# expansion-sn76489-kempton-sd-rev4b.net
KiCad netlist of a schematic drawn in EAGLE
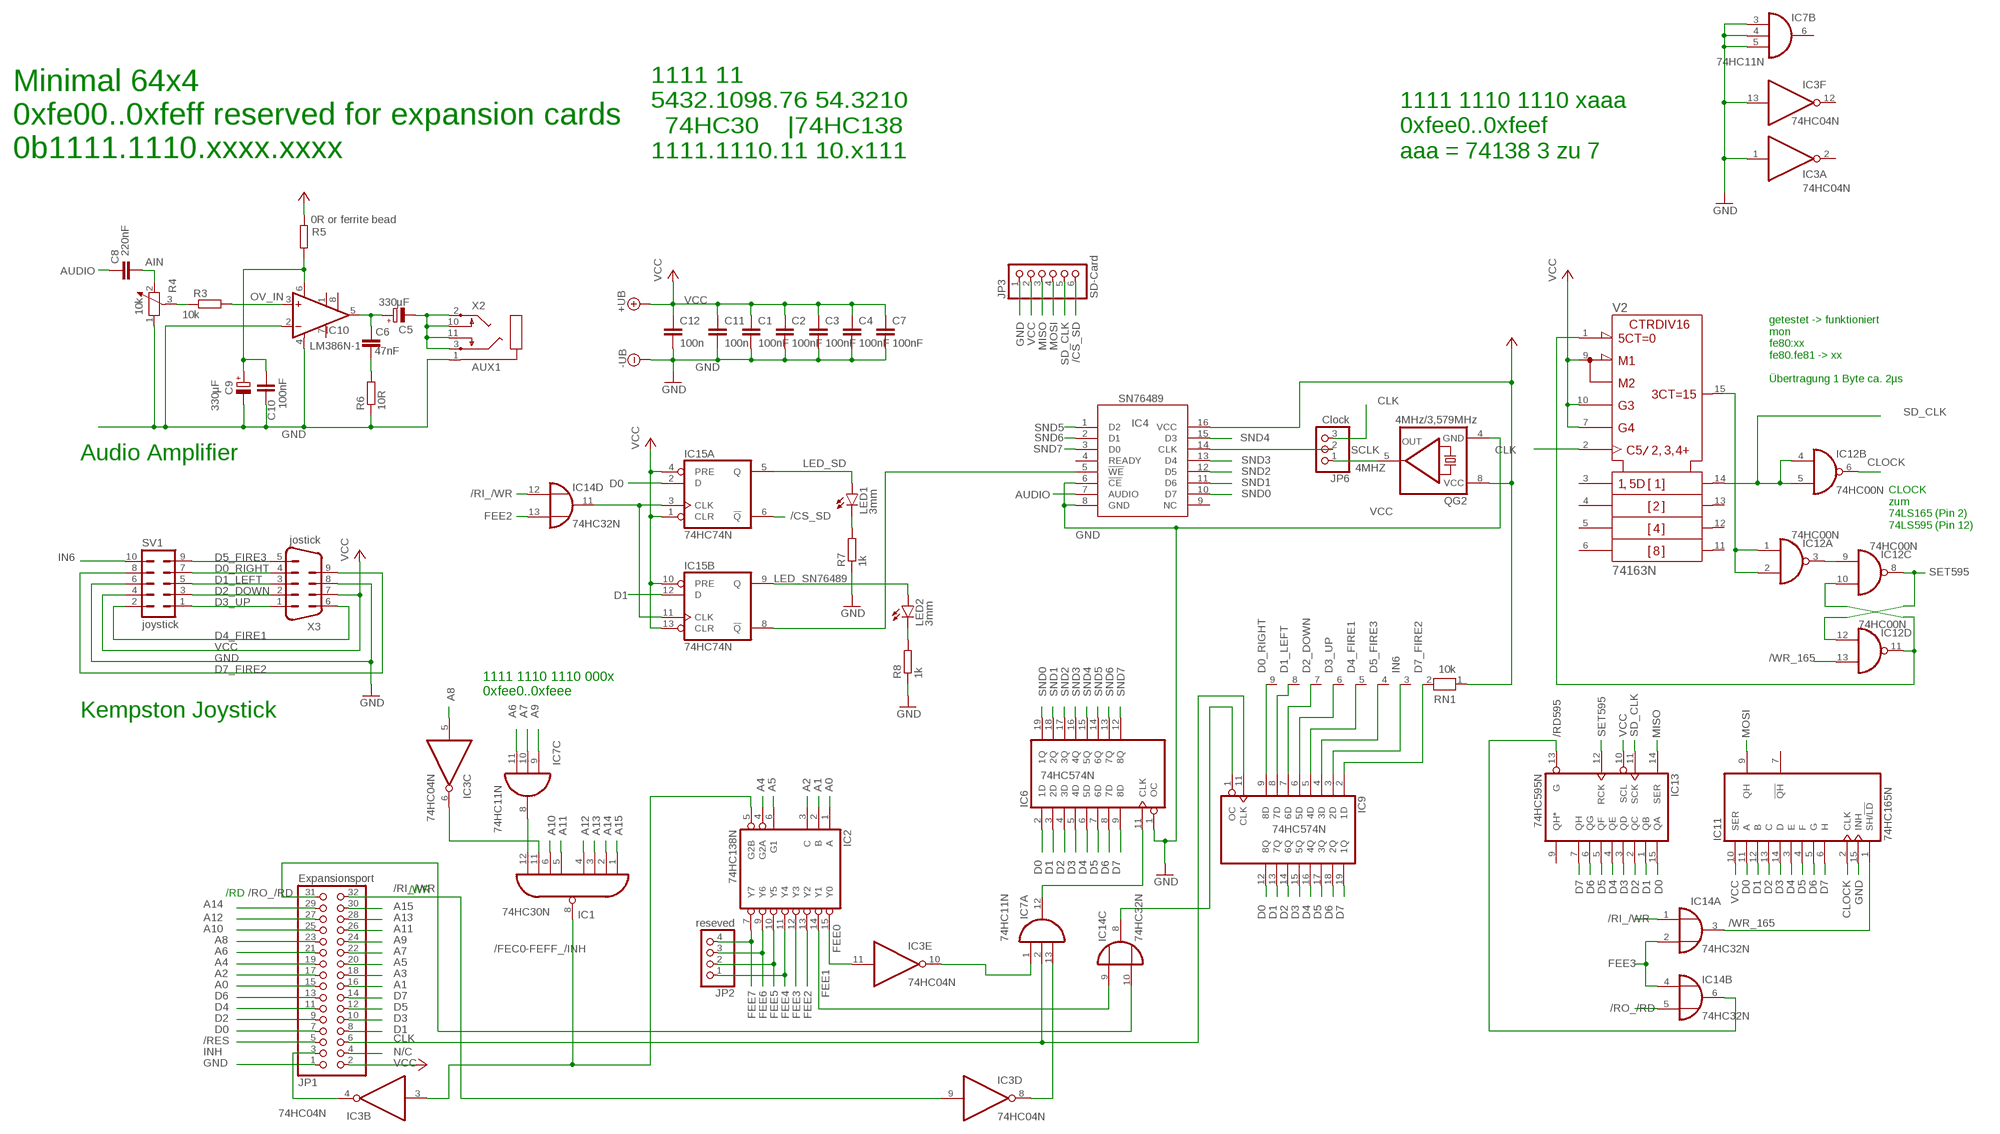
[diagram p0: schematic, sheet 1]

(export (version "E")
  (design (tool "Eeschema 10.0.6"))
  (components
    (comp (ref "C1")
      (value "100nF")
      (footprint "eagle-import:C050-025X075")
      (libsource (lib "eagle-import") (part "C-EU050-025X075"))
    )
    (comp (ref "C2")
      (value "100nF")
      (footprint "eagle-import:C050-025X075")
      (libsource (lib "eagle-import") (part "C-EU050-025X075"))
    )
    (comp (ref "C3")
      (value "100nF")
      (footprint "eagle-import:C050-025X075")
      (libsource (lib "eagle-import") (part "C-EU050-025X075"))
    )
    (comp (ref "C4")
      (value "100nF")
      (footprint "eagle-import:C050-025X075")
      (libsource (lib "eagle-import") (part "C-EU050-025X075"))
    )
    (comp (ref "C5")
      (value "330µF")
      (footprint "eagle-import:E2,5-7")
      (libsource (lib "eagle-import") (part "CPOL-EUE2.5-7"))
    )
    (comp (ref "C6")
      (value "47nF")
      (footprint "eagle-import:C050-025X075")
      (libsource (lib "eagle-import") (part "C-EU050-025X075"))
    )
    (comp (ref "C7")
      (value "100nF")
      (footprint "eagle-import:C050-025X075")
      (libsource (lib "eagle-import") (part "C-EU050-025X075"))
    )
    (comp (ref "C8")
      (value "220nF")
      (footprint "eagle-import:C050-025X075")
      (libsource (lib "eagle-import") (part "C-EU050-025X075"))
    )
    (comp (ref "C9")
      (value "330µF")
      (footprint "eagle-import:E2,5-7")
      (libsource (lib "eagle-import") (part "CPOL-EUE2.5-7"))
    )
    (comp (ref "C10")
      (value "100nF")
      (footprint "eagle-import:C050-025X075")
      (libsource (lib "eagle-import") (part "C-EU050-025X075"))
    )
    (comp (ref "C11")
      (value "100n")
      (footprint "eagle-import:C050-025X075")
      (libsource (lib "eagle-import") (part "C-EU050-025X075"))
    )
    (comp (ref "C12")
      (value "100n")
      (footprint "eagle-import:C050-025X075")
      (libsource (lib "eagle-import") (part "C-EU050-025X075"))
    )
    (comp (ref "IC1")
      (value "74HC30N")
      (footprint "eagle-import:DIL14")
      (libsource (lib "eagle-import") (part "7430NHC"))
    )
    (comp (ref "IC2")
      (value "74HC138N")
      (footprint "eagle-import:DIL16")
      (libsource (lib "eagle-import") (part "74138NHC"))
    )
    (comp (ref "IC3")
      (value "74HC04N")
      (footprint "eagle-import:DIL14")
      (libsource (lib "eagle-import") (part "7404NHC"))
    )
    (comp (ref "IC4")
      (value "SN76489")
      (footprint "eagle-import:ALEX-PARTS_DIL16")
      (libsource (lib "eagle-import") (part "ALEX-PARTS_SN76489AN"))
    )
    (comp (ref "IC6")
      (value "74HC574N")
      (footprint "eagle-import:DIL20")
      (libsource (lib "eagle-import") (part "74574NHC"))
    )
    (comp (ref "IC7")
      (value "74HC11N")
      (footprint "eagle-import:DIL14")
      (libsource (lib "eagle-import") (part "7411NHC"))
    )
    (comp (ref "IC9")
      (value "74HC574N")
      (footprint "eagle-import:DIL20")
      (libsource (lib "eagle-import") (part "74574NHC"))
    )
    (comp (ref "IC10")
      (value "LM386N-1")
      (footprint "eagle-import:DIL08")
      (libsource (lib "eagle-import") (part "LM386?-N1"))
    )
    (comp (ref "IC11")
      (value "74HC165N")
      (footprint "eagle-import:DIL16")
      (libsource (lib "eagle-import") (part "74165NHC"))
    )
    (comp (ref "IC12")
      (value "74HC00N")
      (footprint "eagle-import:DIL14")
      (libsource (lib "eagle-import") (part "7400NHC"))
    )
    (comp (ref "IC13")
      (value "74HC595N")
      (footprint "eagle-import:DIL16")
      (libsource (lib "eagle-import") (part "74595NHC"))
    )
    (comp (ref "IC14")
      (value "74HC32N")
      (footprint "eagle-import:DIL14")
      (libsource (lib "eagle-import") (part "7432NHC"))
    )
    (comp (ref "IC15")
      (value "74HC74N")
      (footprint "eagle-import:DIL14")
      (libsource (lib "eagle-import") (part "7474NHC"))
    )
    (comp (ref "JP1")
      (value "Expansionsport")
      (footprint "eagle-import:2X16")
      (libsource (lib "eagle-import") (part "PINHD-2X16"))
    )
    (comp (ref "JP2")
      (value "reseved")
      (footprint "eagle-import:1X04")
      (libsource (lib "eagle-import") (part "PINHD-1X4"))
    )
    (comp (ref "JP3")
      (value "SD-Card")
      (footprint "eagle-import:1X06")
      (libsource (lib "eagle-import") (part "PINHD-1X6"))
    )
    (comp (ref "JP6")
      (value "Clock")
      (footprint "eagle-import:1X03")
      (libsource (lib "eagle-import") (part "PINHD-1X3"))
    )
    (comp (ref "LED1")
      (value "3mm")
      (footprint "eagle-import:LED3MM")
      (libsource (lib "eagle-import") (part "LED3MM"))
    )
    (comp (ref "LED2")
      (value "3mm")
      (footprint "eagle-import:LED3MM")
      (libsource (lib "eagle-import") (part "LED3MM"))
    )
    (comp (ref "QG2")
      (value "4MHz/3,579MHz")
      (footprint "eagle-import:DIL08S")
      (libsource (lib "eagle-import") (part "QG5460"))
    )
    (comp (ref "R3")
      (value "10k")
      (footprint "eagle-import:0207_10")
      (libsource (lib "eagle-import") (part "R-EU_0207/10"))
    )
    (comp (ref "R4")
      (value "10k")
      (footprint "eagle-import:PT-10S")
      (libsource (lib "eagle-import") (part "POTENTIOMETER_PT-10S"))
    )
    (comp (ref "R5")
      (value "0R or ferrite bead")
      (footprint "eagle-import:0207_10")
      (libsource (lib "eagle-import") (part "R-EU_0207/10"))
    )
    (comp (ref "R6")
      (value "10R")
      (footprint "eagle-import:0207_10")
      (libsource (lib "eagle-import") (part "R-EU_0207/10"))
    )
    (comp (ref "R7")
      (value "1k")
      (footprint "eagle-import:0207_10")
      (libsource (lib "eagle-import") (part "R-EU_0207/10"))
    )
    (comp (ref "R8")
      (value "1k")
      (footprint "eagle-import:0207_10")
      (libsource (lib "eagle-import") (part "R-EU_0207/10"))
    )
    (comp (ref "RN1")
      (value "10k")
      (footprint "eagle-import:RN-9")
      (libsource (lib "eagle-import") (part "RN08"))
    )
    (comp (ref "SV1")
      (value "joystick")
      (footprint "eagle-import:ML10")
      (libsource (lib "eagle-import") (part "ML10"))
    )
    (comp (ref "V2")
      (value "74163N")
      (footprint "eagle-import:DIL16")
      (libsource (lib "eagle-import") (part "74163N"))
    )
    (comp (ref "X2")
      (value "AUX1")
      (footprint "eagle-import:SJ1-352XN")
      (libsource (lib "eagle-import") (part "CON-SJ1-352XNSJ1-352XN"))
    )
    (comp (ref "X3")
      (value "jostick")
      (footprint "eagle-import:182-009-MALE")
      (libsource (lib "eagle-import") (part "M09-182"))
    )
  )
  (nets
    (net (code "1") (name "+UB") (class "Default")
      (node (ref "C1") (pin "1") (pinfunction "1_1") (pintype "passive"))
      (node (ref "C11") (pin "1") (pinfunction "1_1") (pintype "passive"))
      (node (ref "C12") (pin "1") (pinfunction "1_1") (pintype "passive"))
      (node (ref "C2") (pin "1") (pinfunction "1_1") (pintype "passive"))
      (node (ref "C3") (pin "1") (pinfunction "1_1") (pintype "passive"))
      (node (ref "C4") (pin "1") (pinfunction "1_1") (pintype "passive"))
      (node (ref "C7") (pin "1") (pinfunction "1_1") (pintype "passive"))
      (node (ref "IC11") (pin "10") (pinfunction "SER_10") (pintype "input"))
      (node (ref "IC13") (pin "10") (pinfunction "SCL_10") (pintype "input"))
      (node (ref "IC15") (pin "1") (pinfunction "CLR_1") (pintype "input"))
      (node (ref "IC15") (pin "10") (pinfunction "PRE_10") (pintype "input"))
      (node (ref "IC15") (pin "13") (pinfunction "CLR_13") (pintype "input"))
      (node (ref "IC15") (pin "4") (pinfunction "PRE_4") (pintype "input"))
      (node (ref "IC4") (pin "16") (pinfunction "VCC_16") (pintype "input"))
      (node (ref "JP1") (pin "2") (pinfunction "2_2") (pintype "passive"))
      (node (ref "JP3") (pin "2") (pinfunction "2_2") (pintype "passive"))
      (node (ref "QG2") (pin "8") (pinfunction "VCC_8") (pintype "power_in"))
      (node (ref "R5") (pin "2") (pinfunction "2_2") (pintype "passive"))
      (node (ref "RN1") (pin "1") (pinfunction "1_1") (pintype "passive"))
      (node (ref "SV1") (pin "4") (pinfunction "4_4") (pintype "passive"))
      (node (ref "V2") (pin "10") (pinfunction "ENT_10") (pintype "input"))
      (node (ref "V2") (pin "7") (pinfunction "ENP_7") (pintype "input"))
      (node (ref "V2") (pin "9") (pinfunction "~{LOAD}_9") (pintype "input"))
      (node (ref "X3") (pin "7") (pinfunction "7_7") (pintype "passive"))
    )
    (net (code "2") (name "-UB") (class "Default")
      (node (ref "C1") (pin "2") (pinfunction "2_2") (pintype "passive"))
      (node (ref "C10") (pin "2") (pinfunction "2_2") (pintype "passive"))
      (node (ref "C11") (pin "2") (pinfunction "2_2") (pintype "passive"))
      (node (ref "C12") (pin "2") (pinfunction "2_2") (pintype "passive"))
      (node (ref "C2") (pin "2") (pinfunction "2_2") (pintype "passive"))
      (node (ref "C3") (pin "2") (pinfunction "2_2") (pintype "passive"))
      (node (ref "C4") (pin "2") (pinfunction "2_2") (pintype "passive"))
      (node (ref "C7") (pin "2") (pinfunction "2_2") (pintype "passive"))
      (node (ref "C9") (pin "-") (pinfunction "-_-") (pintype "passive"))
      (node (ref "IC10") (pin "2") (pinfunction "-IN_2") (pintype "input"))
      (node (ref "IC10") (pin "4") (pinfunction "GND_4") (pintype "power_in"))
      (node (ref "IC11") (pin "15") (pinfunction "INH_15") (pintype "input"))
      (node (ref "IC3") (pin "1") (pinfunction "I_1") (pintype "input"))
      (node (ref "IC3") (pin "13") (pinfunction "I_13") (pintype "input"))
      (node (ref "IC4") (pin "6") (pinfunction "~{CE}_6") (pintype "input"))
      (node (ref "IC4") (pin "8") (pinfunction "GND_8") (pintype "power_in"))
      (node (ref "IC6") (pin "1") (pinfunction "OC_1") (pintype "input"))
      (node (ref "IC7") (pin "3") (pinfunction "I0_3") (pintype "input"))
      (node (ref "IC7") (pin "4") (pinfunction "I1_4") (pintype "input"))
      (node (ref "IC7") (pin "5") (pinfunction "I2_5") (pintype "input"))
      (node (ref "JP1") (pin "1") (pinfunction "1_1") (pintype "passive"))
      (node (ref "JP3") (pin "1") (pinfunction "1_1") (pintype "passive"))
      (node (ref "QG2") (pin "4") (pinfunction "GND_4") (pintype "power_in"))
      (node (ref "R4") (pin "1") (pinfunction "1_1") (pintype "passive"))
      (node (ref "R6") (pin "1") (pinfunction "1_1") (pintype "passive"))
      (node (ref "R7") (pin "1") (pinfunction "1_1") (pintype "passive"))
      (node (ref "R8") (pin "1") (pinfunction "1_1") (pintype "passive"))
      (node (ref "SV1") (pin "6") (pinfunction "6_6") (pintype "passive"))
      (node (ref "X2") (pin "1") (pinfunction "1_1") (pintype "passive"))
      (node (ref "X3") (pin "8") (pinfunction "8_8") (pintype "passive"))
    )
    (net (code "3") (name "/4MHZ") (class "Default")
      (node (ref "JP6") (pin "1") (pinfunction "1_1") (pintype "passive"))
      (node (ref "QG2") (pin "5") (pinfunction "OUT_5") (pintype "output"))
    )
    (net (code "4") (name "/A0") (class "Default")
      (node (ref "IC2") (pin "1") (pinfunction "A_1") (pintype "input"))
      (node (ref "JP1") (pin "15") (pinfunction "15_15") (pintype "passive"))
    )
    (net (code "5") (name "/A1") (class "Default")
      (node (ref "IC2") (pin "2") (pinfunction "B_2") (pintype "input"))
      (node (ref "JP1") (pin "16") (pinfunction "16_16") (pintype "passive"))
    )
    (net (code "6") (name "/A2") (class "Default")
      (node (ref "IC2") (pin "3") (pinfunction "C_3") (pintype "input"))
      (node (ref "JP1") (pin "17") (pinfunction "17_17") (pintype "passive"))
    )
    (net (code "7") (name "/A3") (class "Default")
      (node (ref "JP1") (pin "18") (pinfunction "18_18") (pintype "passive"))
    )
    (net (code "8") (name "/A4") (class "Default")
      (node (ref "IC2") (pin "4") (pinfunction "G2A_4") (pintype "input"))
      (node (ref "JP1") (pin "19") (pinfunction "19_19") (pintype "passive"))
    )
    (net (code "9") (name "/A5") (class "Default")
      (node (ref "IC2") (pin "6") (pinfunction "G1_6") (pintype "input"))
      (node (ref "JP1") (pin "20") (pinfunction "20_20") (pintype "passive"))
    )
    (net (code "10") (name "/A6") (class "Default")
      (node (ref "IC7") (pin "11") (pinfunction "I2_11") (pintype "input"))
      (node (ref "JP1") (pin "21") (pinfunction "21_21") (pintype "passive"))
    )
    (net (code "11") (name "/A7") (class "Default")
      (node (ref "IC7") (pin "10") (pinfunction "I1_10") (pintype "input"))
      (node (ref "JP1") (pin "22") (pinfunction "22_22") (pintype "passive"))
    )
    (net (code "12") (name "/A8") (class "Default")
      (node (ref "IC3") (pin "5") (pinfunction "I_5") (pintype "input"))
      (node (ref "JP1") (pin "23") (pinfunction "23_23") (pintype "passive"))
    )
    (net (code "13") (name "/A9") (class "Default")
      (node (ref "IC7") (pin "9") (pinfunction "I0_9") (pintype "input"))
      (node (ref "JP1") (pin "24") (pinfunction "24_24") (pintype "passive"))
    )
    (net (code "14") (name "/A10") (class "Default")
      (node (ref "IC1") (pin "6") (pinfunction "I5_6") (pintype "input"))
      (node (ref "JP1") (pin "25") (pinfunction "25_25") (pintype "passive"))
    )
    (net (code "15") (name "/A11") (class "Default")
      (node (ref "IC1") (pin "5") (pinfunction "I4_5") (pintype "input"))
      (node (ref "JP1") (pin "26") (pinfunction "26_26") (pintype "passive"))
    )
    (net (code "16") (name "/A12") (class "Default")
      (node (ref "IC1") (pin "4") (pinfunction "I3_4") (pintype "input"))
      (node (ref "JP1") (pin "27") (pinfunction "27_27") (pintype "passive"))
    )
    (net (code "17") (name "/A13") (class "Default")
      (node (ref "IC1") (pin "3") (pinfunction "I2_3") (pintype "input"))
      (node (ref "JP1") (pin "28") (pinfunction "28_28") (pintype "passive"))
    )
    (net (code "18") (name "/A14") (class "Default")
      (node (ref "IC1") (pin "2") (pinfunction "I1_2") (pintype "input"))
      (node (ref "JP1") (pin "29") (pinfunction "29_29") (pintype "passive"))
    )
    (net (code "19") (name "/A15") (class "Default")
      (node (ref "IC1") (pin "1") (pinfunction "I0_1") (pintype "input"))
      (node (ref "JP1") (pin "30") (pinfunction "30_30") (pintype "passive"))
    )
    (net (code "20") (name "/AIN") (class "Default")
      (node (ref "C8") (pin "2") (pinfunction "2_2") (pintype "passive"))
      (node (ref "R4") (pin "2") (pinfunction "2_2") (pintype "passive"))
    )
    (net (code "21") (name "/AUDIO") (class "Default")
      (node (ref "C8") (pin "1") (pinfunction "1_1") (pintype "passive"))
      (node (ref "IC4") (pin "7") (pinfunction "AUDIO_7") (pintype "output"))
    )
    (net (code "22") (name "/CLK") (class "Default")
      (node (ref "IC7") (pin "2") (pinfunction "I1_2") (pintype "input"))
      (node (ref "IC9") (pin "11") (pinfunction "CLK_11") (pintype "input"))
      (node (ref "JP1") (pin "6") (pinfunction "6_6") (pintype "passive"))
      (node (ref "JP6") (pin "3") (pinfunction "3_3") (pintype "passive"))
      (node (ref "V2") (pin "2") (pinfunction "CLK_2") (pintype "input"))
    )
    (net (code "23") (name "/CLOCK") (class "Default")
      (node (ref "IC11") (pin "2") (pinfunction "CLK_2") (pintype "input"))
      (node (ref "IC12") (pin "6") (pinfunction "O_6") (pintype "output"))
    )
    (net (code "24") (name "/D0") (class "Default")
      (node (ref "IC11") (pin "11") (pinfunction "A_11") (pintype "input"))
      (node (ref "IC13") (pin "15") (pinfunction "QA_15") (pintype "tri_state"))
      (node (ref "IC15") (pin "2") (pinfunction "D_2") (pintype "input"))
      (node (ref "IC6") (pin "2") (pinfunction "1D_2") (pintype "input"))
      (node (ref "IC9") (pin "12") (pinfunction "8Q_12") (pintype "tri_state"))
      (node (ref "JP1") (pin "7") (pinfunction "7_7") (pintype "passive"))
    )
    (net (code "25") (name "/D0_RIGHT") (class "Default")
      (node (ref "IC9") (pin "9") (pinfunction "8D_9") (pintype "input"))
      (node (ref "RN1") (pin "9") (pinfunction "9_9") (pintype "passive"))
      (node (ref "SV1") (pin "7") (pinfunction "7_7") (pintype "passive"))
      (node (ref "X3") (pin "4") (pinfunction "4_4") (pintype "passive"))
    )
    (net (code "26") (name "/D1") (class "Default")
      (node (ref "IC11") (pin "12") (pinfunction "B_12") (pintype "input"))
      (node (ref "IC13") (pin "1") (pinfunction "QB_1") (pintype "tri_state"))
      (node (ref "IC15") (pin "12") (pinfunction "D_12") (pintype "input"))
      (node (ref "IC6") (pin "3") (pinfunction "2D_3") (pintype "input"))
      (node (ref "IC9") (pin "13") (pinfunction "7Q_13") (pintype "tri_state"))
      (node (ref "JP1") (pin "8") (pinfunction "8_8") (pintype "passive"))
    )
    (net (code "27") (name "/D1_LEFT") (class "Default")
      (node (ref "IC9") (pin "8") (pinfunction "7D_8") (pintype "input"))
      (node (ref "RN1") (pin "8") (pinfunction "8_8") (pintype "passive"))
      (node (ref "SV1") (pin "5") (pinfunction "5_5") (pintype "passive"))
      (node (ref "X3") (pin "3") (pinfunction "3_3") (pintype "passive"))
    )
    (net (code "28") (name "/D2") (class "Default")
      (node (ref "IC11") (pin "13") (pinfunction "C_13") (pintype "input"))
      (node (ref "IC13") (pin "2") (pinfunction "QC_2") (pintype "tri_state"))
      (node (ref "IC6") (pin "4") (pinfunction "3D_4") (pintype "input"))
      (node (ref "IC9") (pin "14") (pinfunction "6Q_14") (pintype "tri_state"))
      (node (ref "JP1") (pin "9") (pinfunction "9_9") (pintype "passive"))
    )
    (net (code "29") (name "/D2_DOWN") (class "Default")
      (node (ref "IC9") (pin "7") (pinfunction "6D_7") (pintype "input"))
      (node (ref "RN1") (pin "7") (pinfunction "7_7") (pintype "passive"))
      (node (ref "SV1") (pin "3") (pinfunction "3_3") (pintype "passive"))
      (node (ref "X3") (pin "2") (pinfunction "2_2") (pintype "passive"))
    )
    (net (code "30") (name "/D3") (class "Default")
      (node (ref "IC11") (pin "14") (pinfunction "D_14") (pintype "input"))
      (node (ref "IC13") (pin "3") (pinfunction "QD_3") (pintype "tri_state"))
      (node (ref "IC6") (pin "5") (pinfunction "4D_5") (pintype "input"))
      (node (ref "IC9") (pin "15") (pinfunction "5Q_15") (pintype "tri_state"))
      (node (ref "JP1") (pin "10") (pinfunction "10_10") (pintype "passive"))
    )
    (net (code "31") (name "/D3_UP") (class "Default")
      (node (ref "IC9") (pin "6") (pinfunction "5D_6") (pintype "input"))
      (node (ref "RN1") (pin "6") (pinfunction "6_6") (pintype "passive"))
      (node (ref "SV1") (pin "1") (pinfunction "1_1") (pintype "passive"))
      (node (ref "X3") (pin "1") (pinfunction "1_1") (pintype "passive"))
    )
    (net (code "32") (name "/D4") (class "Default")
      (node (ref "IC11") (pin "3") (pinfunction "E_3") (pintype "input"))
      (node (ref "IC13") (pin "4") (pinfunction "QE_4") (pintype "tri_state"))
      (node (ref "IC6") (pin "6") (pinfunction "5D_6") (pintype "input"))
      (node (ref "IC9") (pin "16") (pinfunction "4Q_16") (pintype "tri_state"))
      (node (ref "JP1") (pin "11") (pinfunction "11_11") (pintype "passive"))
    )
    (net (code "33") (name "/D4_FIRE1") (class "Default")
      (node (ref "IC9") (pin "5") (pinfunction "4D_5") (pintype "input"))
      (node (ref "RN1") (pin "5") (pinfunction "5_5") (pintype "passive"))
      (node (ref "SV1") (pin "2") (pinfunction "2_2") (pintype "passive"))
      (node (ref "X3") (pin "6") (pinfunction "6_6") (pintype "passive"))
    )
    (net (code "34") (name "/D5") (class "Default")
      (node (ref "IC11") (pin "4") (pinfunction "F_4") (pintype "input"))
      (node (ref "IC13") (pin "5") (pinfunction "QF_5") (pintype "tri_state"))
      (node (ref "IC6") (pin "7") (pinfunction "6D_7") (pintype "input"))
      (node (ref "IC9") (pin "17") (pinfunction "3Q_17") (pintype "tri_state"))
      (node (ref "JP1") (pin "12") (pinfunction "12_12") (pintype "passive"))
    )
    (net (code "35") (name "/D5_FIRE3") (class "Default")
      (node (ref "IC9") (pin "4") (pinfunction "3D_4") (pintype "input"))
      (node (ref "RN1") (pin "4") (pinfunction "4_4") (pintype "passive"))
      (node (ref "SV1") (pin "9") (pinfunction "9_9") (pintype "passive"))
      (node (ref "X3") (pin "5") (pinfunction "5_5") (pintype "passive"))
    )
    (net (code "36") (name "/D6") (class "Default")
      (node (ref "IC11") (pin "5") (pinfunction "G_5") (pintype "input"))
      (node (ref "IC13") (pin "6") (pinfunction "QG_6") (pintype "tri_state"))
      (node (ref "IC6") (pin "8") (pinfunction "7D_8") (pintype "input"))
      (node (ref "IC9") (pin "18") (pinfunction "2Q_18") (pintype "tri_state"))
      (node (ref "JP1") (pin "13") (pinfunction "13_13") (pintype "passive"))
    )
    (net (code "37") (name "/D7") (class "Default")
      (node (ref "IC11") (pin "6") (pinfunction "H_6") (pintype "input"))
      (node (ref "IC13") (pin "7") (pinfunction "QH_7") (pintype "tri_state"))
      (node (ref "IC6") (pin "9") (pinfunction "8D_9") (pintype "input"))
      (node (ref "IC9") (pin "19") (pinfunction "1Q_19") (pintype "tri_state"))
      (node (ref "JP1") (pin "14") (pinfunction "14_14") (pintype "passive"))
    )
    (net (code "38") (name "/D7_FIRE2") (class "Default")
      (node (ref "IC9") (pin "2") (pinfunction "1D_2") (pintype "input"))
      (node (ref "RN1") (pin "2") (pinfunction "2_2") (pintype "passive"))
      (node (ref "SV1") (pin "8") (pinfunction "8_8") (pintype "passive"))
      (node (ref "X3") (pin "9") (pinfunction "9_9") (pintype "passive"))
    )
    (net (code "39") (name "/FEE0") (class "Default")
      (node (ref "IC2") (pin "15") (pinfunction "Y0_15") (pintype "output"))
      (node (ref "IC3") (pin "11") (pinfunction "I_11") (pintype "input"))
    )
    (net (code "40") (name "/FEE1") (class "Default")
      (node (ref "IC14") (pin "9") (pinfunction "I0_9") (pintype "input"))
      (node (ref "IC2") (pin "14") (pinfunction "Y1_14") (pintype "output"))
    )
    (net (code "41") (name "/FEE2") (class "Default")
      (node (ref "IC14") (pin "13") (pinfunction "I1_13") (pintype "input"))
      (node (ref "IC2") (pin "13") (pinfunction "Y2_13") (pintype "output"))
    )
    (net (code "42") (name "/FEE3") (class "Default")
      (node (ref "IC14") (pin "2") (pinfunction "I1_2") (pintype "input"))
      (node (ref "IC14") (pin "4") (pinfunction "I0_4") (pintype "input"))
      (node (ref "IC2") (pin "12") (pinfunction "Y3_12") (pintype "output"))
    )
    (net (code "43") (name "/FEE4") (class "Default")
      (node (ref "IC2") (pin "11") (pinfunction "Y4_11") (pintype "output"))
      (node (ref "JP2") (pin "1") (pinfunction "1_1") (pintype "passive"))
    )
    (net (code "44") (name "/FEE5") (class "Default")
      (node (ref "IC2") (pin "10") (pinfunction "Y5_10") (pintype "output"))
      (node (ref "JP2") (pin "2") (pinfunction "2_2") (pintype "passive"))
    )
    (net (code "45") (name "/FEE6") (class "Default")
      (node (ref "IC2") (pin "9") (pinfunction "Y6_9") (pintype "output"))
      (node (ref "JP2") (pin "3") (pinfunction "3_3") (pintype "passive"))
    )
    (net (code "46") (name "/FEE7") (class "Default")
      (node (ref "IC2") (pin "7") (pinfunction "Y7_7") (pintype "output"))
      (node (ref "JP2") (pin "4") (pinfunction "4_4") (pintype "passive"))
    )
    (net (code "47") (name "/IN6") (class "Default")
      (node (ref "IC9") (pin "3") (pinfunction "2D_3") (pintype "input"))
      (node (ref "RN1") (pin "3") (pinfunction "3_3") (pintype "passive"))
      (node (ref "SV1") (pin "10") (pinfunction "10_10") (pintype "passive"))
    )
    (net (code "48") (name "/INH") (class "Default")
      (node (ref "IC3") (pin "4") (pinfunction "O_4") (pintype "output"))
      (node (ref "JP1") (pin "3") (pinfunction "3_3") (pintype "passive"))
    )
    (net (code "49") (name "/LED_SD") (class "Default")
      (node (ref "IC15") (pin "5") (pinfunction "Q_5") (pintype "output"))
      (node (ref "LED1") (pin "A") (pinfunction "A_A") (pintype "passive"))
    )
    (net (code "50") (name "/LED_SN76489") (class "Default")
      (node (ref "IC15") (pin "9") (pinfunction "Q_9") (pintype "output"))
      (node (ref "LED2") (pin "A") (pinfunction "A_A") (pintype "passive"))
    )
    (net (code "51") (name "/MISO") (class "Default")
      (node (ref "IC13") (pin "14") (pinfunction "SER_14") (pintype "input"))
      (node (ref "JP3") (pin "3") (pinfunction "3_3") (pintype "passive"))
    )
    (net (code "52") (name "/MOSI") (class "Default")
      (node (ref "IC11") (pin "9") (pinfunction "QH_9") (pintype "output"))
      (node (ref "JP3") (pin "4") (pinfunction "4_4") (pintype "passive"))
    )
    (net (code "53") (name "/N{slash}C") (class "Default")
      (node (ref "JP1") (pin "4") (pinfunction "4_4") (pintype "passive"))
    )
    (net (code "54") (name "/OV_IN") (class "Default")
      (node (ref "IC10") (pin "3") (pinfunction "+IN_3") (pintype "input"))
      (node (ref "R3") (pin "2") (pinfunction "2_2") (pintype "passive"))
    )
    (net (code "55") (name "/SCLK") (class "Default")
      (node (ref "IC4") (pin "14") (pinfunction "CLK_14") (pintype "input"))
      (node (ref "JP6") (pin "2") (pinfunction "2_2") (pintype "passive"))
    )
    (net (code "56") (name "/SD_CLK") (class "Default")
      (node (ref "IC12") (pin "4") (pinfunction "I0_4") (pintype "input"))
      (node (ref "IC12") (pin "5") (pinfunction "I1_5") (pintype "input"))
      (node (ref "IC13") (pin "11") (pinfunction "SCK_11") (pintype "input"))
      (node (ref "JP3") (pin "5") (pinfunction "5_5") (pintype "passive"))
      (node (ref "V2") (pin "14") (pinfunction "QA_14") (pintype "output"))
    )
    (net (code "57") (name "/SET595") (class "Default")
      (node (ref "IC12") (pin "12") (pinfunction "I0_12") (pintype "input"))
      (node (ref "IC12") (pin "8") (pinfunction "O_8") (pintype "output"))
      (node (ref "IC13") (pin "12") (pinfunction "RCK_12") (pintype "input"))
    )
    (net (code "58") (name "/SND0") (class "Default")
      (node (ref "IC4") (pin "10") (pinfunction "D7_10") (pintype "input"))
      (node (ref "IC6") (pin "19") (pinfunction "1Q_19") (pintype "tri_state"))
    )
    (net (code "59") (name "/SND1") (class "Default")
      (node (ref "IC4") (pin "11") (pinfunction "D6_11") (pintype "input"))
      (node (ref "IC6") (pin "18") (pinfunction "2Q_18") (pintype "tri_state"))
    )
    (net (code "60") (name "/SND2") (class "Default")
      (node (ref "IC4") (pin "12") (pinfunction "D5_12") (pintype "input"))
      (node (ref "IC6") (pin "17") (pinfunction "3Q_17") (pintype "tri_state"))
    )
    (net (code "61") (name "/SND3") (class "Default")
      (node (ref "IC4") (pin "13") (pinfunction "D4_13") (pintype "input"))
      (node (ref "IC6") (pin "16") (pinfunction "4Q_16") (pintype "tri_state"))
    )
    (net (code "62") (name "/SND4") (class "Default")
      (node (ref "IC4") (pin "15") (pinfunction "D3_15") (pintype "input"))
      (node (ref "IC6") (pin "15") (pinfunction "5Q_15") (pintype "tri_state"))
    )
    (net (code "63") (name "/SND5") (class "Default")
      (node (ref "IC4") (pin "1") (pinfunction "D2_1") (pintype "input"))
      (node (ref "IC6") (pin "14") (pinfunction "6Q_14") (pintype "tri_state"))
    )
    (net (code "64") (name "/SND6") (class "Default")
      (node (ref "IC4") (pin "2") (pinfunction "D1_2") (pintype "input"))
      (node (ref "IC6") (pin "13") (pinfunction "7Q_13") (pintype "tri_state"))
    )
    (net (code "65") (name "/SND7") (class "Default")
      (node (ref "IC4") (pin "3") (pinfunction "D0_3") (pintype "input"))
      (node (ref "IC6") (pin "12") (pinfunction "8Q_12") (pintype "tri_state"))
    )
    (net (code "66") (name "/{slash}CS_SD") (class "Default")
      (node (ref "IC15") (pin "6") (pinfunction "~{Q}_6") (pintype "output"))
      (node (ref "JP3") (pin "6") (pinfunction "6_6") (pintype "passive"))
    )
    (net (code "67") (name "/{slash}FEC0-FEFF_{slash}INH") (class "Default")
      (node (ref "IC1") (pin "8") (pinfunction "O_8") (pintype "output"))
      (node (ref "IC2") (pin "5") (pinfunction "G2B_5") (pintype "input"))
      (node (ref "IC3") (pin "3") (pinfunction "I_3") (pintype "input"))
    )
    (net (code "68") (name "/{slash}RD595") (class "Default")
      (node (ref "IC13") (pin "13") (pinfunction "G_13") (pintype "input"))
      (node (ref "IC14") (pin "6") (pinfunction "O_6") (pintype "output"))
    )
    (net (code "69") (name "/{slash}RES") (class "Default")
      (node (ref "JP1") (pin "5") (pinfunction "5_5") (pintype "passive"))
    )
    (net (code "70") (name "/{slash}RI_{slash}WR") (class "Default")
      (node (ref "IC14") (pin "1") (pinfunction "I0_1") (pintype "input"))
      (node (ref "IC14") (pin "12") (pinfunction "I0_12") (pintype "input"))
      (node (ref "IC3") (pin "9") (pinfunction "I_9") (pintype "input"))
      (node (ref "JP1") (pin "32") (pinfunction "32_32") (pintype "passive"))
    )
    (net (code "71") (name "/{slash}RO_{slash}RD") (class "Default")
      (node (ref "IC14") (pin "10") (pinfunction "I1_10") (pintype "input"))
      (node (ref "IC14") (pin "5") (pinfunction "I1_5") (pintype "input"))
      (node (ref "JP1") (pin "31") (pinfunction "31_31") (pintype "passive"))
    )
    (net (code "72") (name "/{slash}WR_165") (class "Default")
      (node (ref "IC11") (pin "1") (pinfunction "SH/~{LD}_1") (pintype "input"))
      (node (ref "IC12") (pin "13") (pinfunction "I1_13") (pintype "input"))
      (node (ref "IC14") (pin "3") (pinfunction "O_3") (pintype "output"))
    )
    (net (code "73") (name "Net-(C5-Pad-)") (class "Default")
      (node (ref "C5") (pin "-") (pinfunction "-_-") (pintype "passive"))
      (node (ref "X2") (pin "10") (pinfunction "10_10") (pintype "passive"))
      (node (ref "X2") (pin "11") (pinfunction "11_11") (pintype "passive"))
      (node (ref "X2") (pin "2") (pinfunction "2_2") (pintype "passive"))
      (node (ref "X2") (pin "3") (pinfunction "3_3") (pintype "passive"))
    )
    (net (code "74") (name "Net-(C6-Pad2)") (class "Default")
      (node (ref "C6") (pin "2") (pinfunction "2_2") (pintype "passive"))
      (node (ref "R6") (pin "2") (pinfunction "2_2") (pintype "passive"))
    )
    (net (code "75") (name "Net-(IC1A-I6)") (class "Default")
      (node (ref "IC1") (pin "11") (pinfunction "I6_11") (pintype "input"))
      (node (ref "IC3") (pin "6") (pinfunction "O_6") (pintype "output"))
    )
    (net (code "76") (name "Net-(IC1A-I7)") (class "Default")
      (node (ref "IC1") (pin "12") (pinfunction "I7_12") (pintype "input"))
      (node (ref "IC7") (pin "8") (pinfunction "O_8") (pintype "output"))
    )
    (net (code "77") (name "Net-(IC3D-O)") (class "Default")
      (node (ref "IC3") (pin "8") (pinfunction "O_8") (pintype "output"))
      (node (ref "IC7") (pin "13") (pinfunction "I2_13") (pintype "input"))
    )
    (net (code "78") (name "Net-(IC3E-O)") (class "Default")
      (node (ref "IC3") (pin "10") (pinfunction "O_10") (pintype "output"))
      (node (ref "IC7") (pin "1") (pinfunction "I0_1") (pintype "input"))
    )
    (net (code "79") (name "Net-(IC6A-CLK)") (class "Default")
      (node (ref "IC6") (pin "11") (pinfunction "CLK_11") (pintype "input"))
      (node (ref "IC7") (pin "12") (pinfunction "O_12") (pintype "output"))
    )
    (net (code "80") (name "Net-(IC10-OUT)") (class "Default")
      (node (ref "C5") (pin "+") (pinfunction "+_+") (pintype "passive"))
      (node (ref "C6") (pin "1") (pinfunction "1_1") (pintype "passive"))
      (node (ref "IC10") (pin "5") (pinfunction "OUT_5") (pintype "output"))
    )
    (net (code "81") (name "Net-(IC10-VS)") (class "Default")
      (node (ref "C10") (pin "1") (pinfunction "1_1") (pintype "passive"))
      (node (ref "C9") (pin "+") (pinfunction "+_+") (pintype "passive"))
      (node (ref "IC10") (pin "6") (pinfunction "VS_6") (pintype "power_in"))
      (node (ref "R5") (pin "1") (pinfunction "1_1") (pintype "passive"))
    )
    (net (code "82") (name "Net-(IC12A-I0)") (class "Default")
      (node (ref "IC12") (pin "1") (pinfunction "I0_1") (pintype "input"))
      (node (ref "IC12") (pin "2") (pinfunction "I1_2") (pintype "input"))
      (node (ref "V2") (pin "15") (pinfunction "RCO_15") (pintype "output"))
    )
    (net (code "83") (name "Net-(IC12A-O)") (class "Default")
      (node (ref "IC12") (pin "3") (pinfunction "O_3") (pintype "output"))
      (node (ref "IC12") (pin "9") (pinfunction "I0_9") (pintype "input"))
    )
    (net (code "84") (name "Net-(IC12C-I1)") (class "Default")
      (node (ref "IC12") (pin "10") (pinfunction "I1_10") (pintype "input"))
      (node (ref "IC12") (pin "11") (pinfunction "O_11") (pintype "output"))
      (node (ref "V2") (pin "1") (pinfunction "~{CLR}_1") (pintype "input"))
    )
    (net (code "85") (name "Net-(IC14C-O)") (class "Default")
      (node (ref "IC14") (pin "8") (pinfunction "O_8") (pintype "output"))
      (node (ref "IC9") (pin "1") (pinfunction "OC_1") (pintype "input"))
    )
    (net (code "86") (name "Net-(IC14D-O)") (class "Default")
      (node (ref "IC14") (pin "11") (pinfunction "O_11") (pintype "output"))
      (node (ref "IC15") (pin "11") (pinfunction "CLK_11") (pintype "input"))
      (node (ref "IC15") (pin "3") (pinfunction "CLK_3") (pintype "input"))
    )
    (net (code "87") (name "Net-(IC15B-~{Q})") (class "Default")
      (node (ref "IC15") (pin "8") (pinfunction "~{Q}_8") (pintype "output"))
      (node (ref "IC4") (pin "5") (pinfunction "~{WE}_5") (pintype "input"))
    )
    (net (code "88") (name "Net-(LED1-C)") (class "Default")
      (node (ref "LED1") (pin "K") (pinfunction "C_K") (pintype "passive"))
      (node (ref "R7") (pin "2") (pinfunction "2_2") (pintype "passive"))
    )
    (net (code "89") (name "Net-(LED2-C)") (class "Default")
      (node (ref "LED2") (pin "K") (pinfunction "C_K") (pintype "passive"))
      (node (ref "R8") (pin "2") (pinfunction "2_2") (pintype "passive"))
    )
    (net (code "90") (name "Net-(R3-Pad1)") (class "Default")
      (node (ref "R3") (pin "1") (pinfunction "1_1") (pintype "passive"))
      (node (ref "R4") (pin "3") (pinfunction "3_3") (pintype "passive"))
    )
    (net (code "91") (name "unconnected-(IC3A-O-Pad2)") (class "Default")
      (node (ref "IC3") (pin "2") (pinfunction "O_2") (pintype "output"))
    )
    (net (code "92") (name "unconnected-(IC3F-O-Pad12)") (class "Default")
      (node (ref "IC3") (pin "12") (pinfunction "O_12") (pintype "output"))
    )
    (net (code "93") (name "unconnected-(IC4-NC-Pad9)") (class "Default")
      (node (ref "IC4") (pin "9") (pinfunction "NC_9") (pintype "no_connect"))
    )
    (net (code "94") (name "unconnected-(IC4-READY-Pad4)") (class "Default")
      (node (ref "IC4") (pin "4") (pinfunction "READY_4") (pintype "output"))
    )
    (net (code "95") (name "unconnected-(IC7B-O-Pad6)") (class "Default")
      (node (ref "IC7") (pin "6") (pinfunction "O_6") (pintype "output"))
    )
    (net (code "96") (name "unconnected-(IC10-BYPASS-Pad7)") (class "Default")
      (node (ref "IC10") (pin "7") (pinfunction "BYPASS_7") (pintype "passive"))
    )
    (net (code "97") (name "unconnected-(IC10-GAIN-Pad1)") (class "Default")
      (node (ref "IC10") (pin "1") (pinfunction "GAIN_1") (pintype "passive"))
    )
    (net (code "98") (name "unconnected-(IC10-GAIN-Pad8)") (class "Default")
      (node (ref "IC10") (pin "8") (pinfunction "GAIN_8") (pintype "passive"))
    )
    (net (code "99") (name "unconnected-(IC11A-~{QH}-Pad7)") (class "Default")
      (node (ref "IC11") (pin "7") (pinfunction "~{QH}_7") (pintype "output"))
    )
    (net (code "100") (name "unconnected-(IC13A-QH*-Pad9)") (class "Default")
      (node (ref "IC13") (pin "9") (pinfunction "QH*_9") (pintype "tri_state"))
    )
    (net (code "101") (name "unconnected-(V2C-A-Pad3)") (class "Default")
      (node (ref "V2") (pin "3") (pinfunction "A_3") (pintype "input"))
    )
    (net (code "102") (name "unconnected-(V2C-B-Pad4)") (class "Default")
      (node (ref "V2") (pin "4") (pinfunction "B_4") (pintype "input"))
    )
    (net (code "103") (name "unconnected-(V2C-C-Pad5)") (class "Default")
      (node (ref "V2") (pin "5") (pinfunction "C_5") (pintype "input"))
    )
    (net (code "104") (name "unconnected-(V2C-D-Pad6)") (class "Default")
      (node (ref "V2") (pin "6") (pinfunction "D_6") (pintype "input"))
    )
    (net (code "105") (name "unconnected-(V2C-QB-Pad13)") (class "Default")
      (node (ref "V2") (pin "13") (pinfunction "QB_13") (pintype "output"))
    )
    (net (code "106") (name "unconnected-(V2C-QC-Pad12)") (class "Default")
      (node (ref "V2") (pin "12") (pinfunction "QC_12") (pintype "output"))
    )
    (net (code "107") (name "unconnected-(V2C-QD-Pad11)") (class "Default")
      (node (ref "V2") (pin "11") (pinfunction "QD_11") (pintype "output"))
    )
  )
)
